# SCore-SR1_2024-11-10.net
KiCad netlist of a schematic drawn in Altium Designer
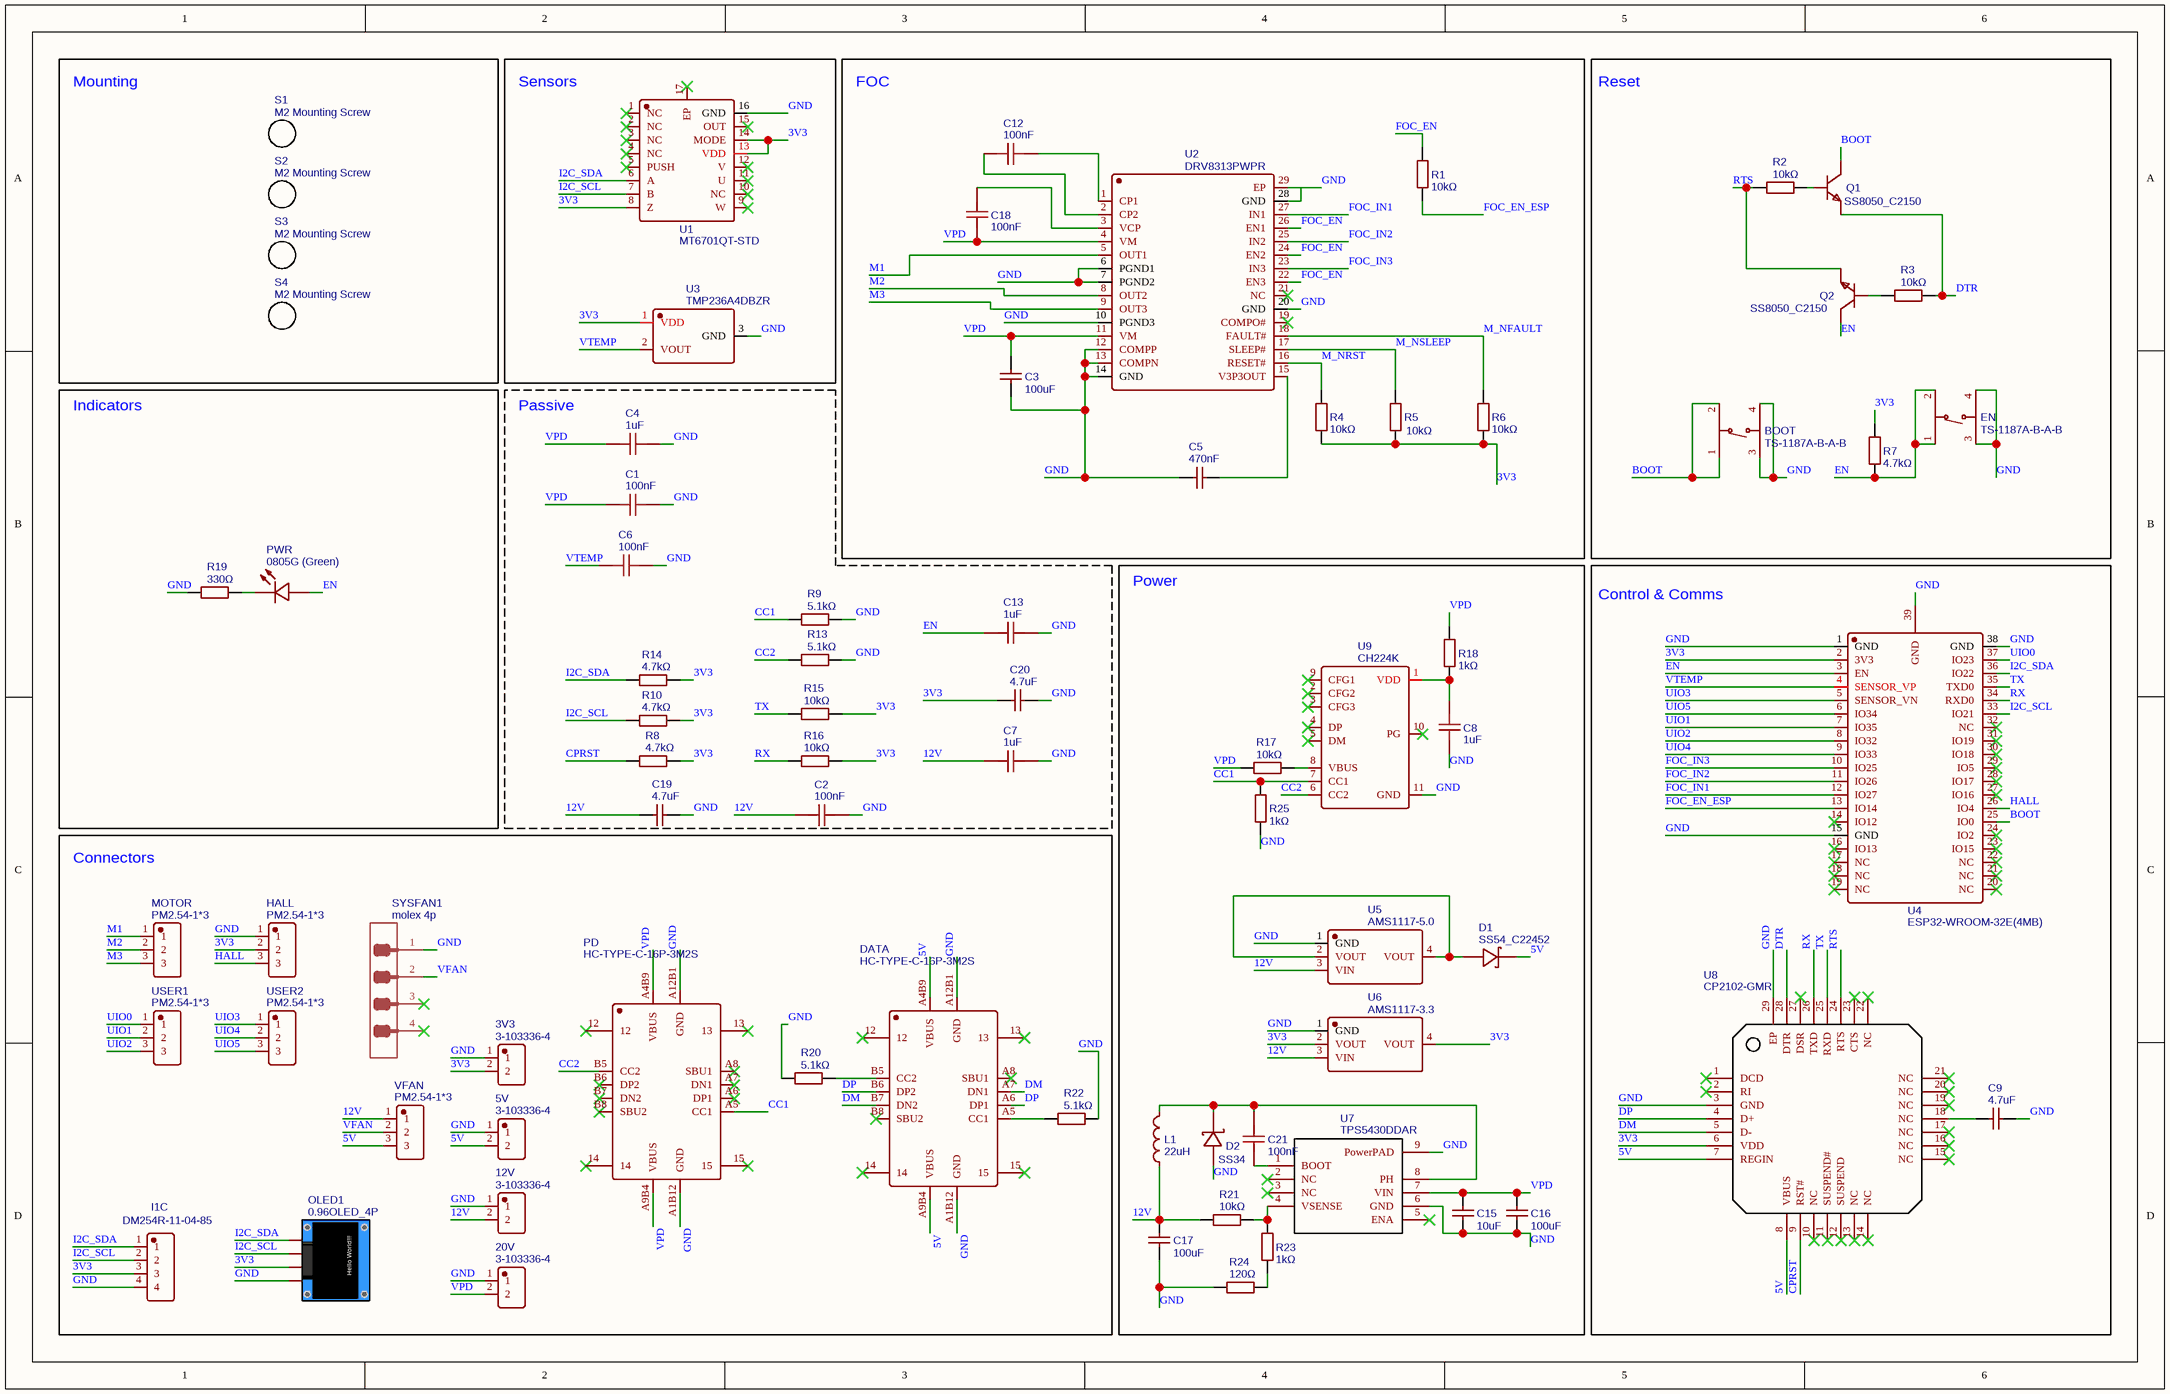
[diagram p0: SCore-SR1_2024-11-10.schdoc]

(export (version "E")
  (design (tool "Eeschema 10.0.6"))
  (components
    (comp (ref "3V3")
      (value "3-103336-4")
      (fields (field (name "MANUFACTURER") "TE Connectivity(泰科电子)") (field (name "CONTRIBUTOR") "lcsc"))
      (libsource (lib "altium-import") (part "root_0_3-103336-4_"))
    )
    (comp (ref "5V")
      (value "3-103336-4")
      (fields (field (name "MANUFACTURER") "TE Connectivity(泰科电子)") (field (name "CONTRIBUTOR") "lcsc"))
      (libsource (lib "altium-import") (part "root_0_3-103336-4_"))
    )
    (comp (ref "12V")
      (value "3-103336-4")
      (fields (field (name "MANUFACTURER") "TE Connectivity(泰科电子)") (field (name "CONTRIBUTOR") "lcsc"))
      (libsource (lib "altium-import") (part "root_0_3-103336-4_"))
    )
    (comp (ref "20V")
      (value "3-103336-4")
      (fields (field (name "MANUFACTURER") "TE Connectivity(泰科电子)") (field (name "CONTRIBUTOR") "lcsc"))
      (libsource (lib "altium-import") (part "root_0_3-103336-4_"))
    )
    (comp (ref "BOOT")
      (value "TS-1187A-B-A-B")
      (fields (field (name "MANUFACTURER") "XKB Connectivity(中国星坤)") (field (name "CONTRIBUTOR") "LCSC"))
      (libsource (lib "altium-import") (part "root_1_TS-1187A-B-A-B_"))
    )
    (comp (ref "C1")
      (value "100nF")
      (fields
        (field (name "MANUFACTURER") "YAGEO(国巨)")
        (field (name "MANUFACTURER PART") "CC0603KRX7R9BB104")
      )
      (libsource (lib "altium-import") (part "root_0_100nF_"))
    )
    (comp (ref "C2")
      (value "100nF")
      (fields
        (field (name "MANUFACTURER") "YAGEO(国巨)")
        (field (name "MANUFACTURER PART") "CC0603KRX7R9BB104")
      )
      (libsource (lib "altium-import") (part "root_0_100nF_"))
    )
    (comp (ref "C3")
      (value "100uF")
      (fields
        (field (name "MANUFACTURER PART") "CL31A107MQHNNNE")
        (field (name "MANUFACTURER") "SAMSUNG(三星)")
      )
      (libsource (lib "altium-import") (part "root_1_100uF_"))
    )
    (comp (ref "C4")
      (value "1uF")
      (fields
        (field (name "MANUFACTURER PART") "CL10A105KB8NNNC")
        (field (name "MANUFACTURER") "SAMSUNG(三星)")
      )
      (libsource (lib "altium-import") (part "root_0_1uF_"))
    )
    (comp (ref "C5")
      (value "470nF")
      (fields
        (field (name "MANUFACTURER PART") "CL21B474KBFNNNE")
        (field (name "MANUFACTURER") "SAMSUNG(三星)")
        (field (name "CONTRIBUTOR") "eisendev")
      )
      (libsource (lib "altium-import") (part "root_3_470nF_"))
    )
    (comp (ref "C6")
      (value "100nF")
      (fields
        (field (name "MANUFACTURER") "YAGEO(国巨)")
        (field (name "MANUFACTURER PART") "CC0603KRX7R9BB104")
      )
      (libsource (lib "altium-import") (part "root_0_100nF_"))
    )
    (comp (ref "C7")
      (value "1uF")
      (fields
        (field (name "MANUFACTURER PART") "CL10A105KB8NNNC")
        (field (name "MANUFACTURER") "SAMSUNG(三星)")
      )
      (libsource (lib "altium-import") (part "root_0_1uF_"))
    )
    (comp (ref "C8")
      (value "1uF")
      (fields
        (field (name "MANUFACTURER PART") "CL10A105KB8NNNC")
        (field (name "MANUFACTURER") "SAMSUNG(三星)")
      )
      (libsource (lib "altium-import") (part "root_1_1uF_"))
    )
    (comp (ref "C9")
      (value "4.7uF")
      (fields
        (field (name "MANUFACTURER PART") "CL21A475KAQNNNE")
        (field (name "MANUFACTURER") "SAMSUNG(三星)")
      )
      (libsource (lib "altium-import") (part "root_0_4.7uF_"))
    )
    (comp (ref "C12")
      (value "100nF")
      (fields
        (field (name "MANUFACTURER") "YAGEO(国巨)")
        (field (name "MANUFACTURER PART") "CC0603KRX7R9BB104")
      )
      (libsource (lib "altium-import") (part "root_0_100nF_"))
    )
    (comp (ref "C13")
      (value "1uF")
      (fields
        (field (name "MANUFACTURER PART") "CL10A105KB8NNNC")
        (field (name "MANUFACTURER") "SAMSUNG(三星)")
      )
      (libsource (lib "altium-import") (part "root_0_1uF_"))
    )
    (comp (ref "C15")
      (value "10uF")
      (fields
        (field (name "MANUFACTURER PART") "CL31A106KBHNNNE")
        (field (name "MANUFACTURER") "SAMSUNG(三星)")
      )
      (libsource (lib "altium-import") (part "root_1_10uF_"))
    )
    (comp (ref "C16")
      (value "100uF")
      (fields
        (field (name "MANUFACTURER PART") "CL31A107MQHNNNE")
        (field (name "MANUFACTURER") "SAMSUNG(三星)")
      )
      (libsource (lib "altium-import") (part "root_1_100uF_"))
    )
    (comp (ref "C17")
      (value "100uF")
      (fields
        (field (name "MANUFACTURER PART") "CL31A107MQHNNNE")
        (field (name "MANUFACTURER") "SAMSUNG(三星)")
      )
      (libsource (lib "altium-import") (part "root_1_100uF_"))
    )
    (comp (ref "C18")
      (value "100nF")
      (fields
        (field (name "MANUFACTURER") "YAGEO(国巨)")
        (field (name "MANUFACTURER PART") "CC0603KRX7R9BB104")
      )
      (libsource (lib "altium-import") (part "root_1_100nF_"))
    )
    (comp (ref "C19")
      (value "4.7uF")
      (fields
        (field (name "MANUFACTURER PART") "CL21A475KAQNNNE")
        (field (name "MANUFACTURER") "SAMSUNG(三星)")
      )
      (libsource (lib "altium-import") (part "root_0_4.7uF_"))
    )
    (comp (ref "C20")
      (value "4.7uF")
      (fields
        (field (name "MANUFACTURER PART") "CL21A475KAQNNNE")
        (field (name "MANUFACTURER") "SAMSUNG(三星)")
      )
      (libsource (lib "altium-import") (part "root_0_4.7uF_"))
    )
    (comp (ref "C21")
      (value "100nF")
      (fields
        (field (name "MANUFACTURER") "YAGEO(国巨)")
        (field (name "MANUFACTURER PART") "CC0603KRX7R9BB104")
      )
      (libsource (lib "altium-import") (part "root_3_100nF_"))
    )
    (comp (ref "D1")
      (value "SS54_C22452")
      (fields
        (field (name "MANUFACTURER PART") "SS54")
        (field (name "MANUFACTURER") "MDD")
        (field (name "CONTRIBUTOR") "mtz8302")
      )
      (libsource (lib "altium-import") (part "root_0_SS54_C22452_"))
    )
    (comp (ref "D2")
      (value "SS34")
      (fields (field (name "MANUFACTURER") "MDD(辰达半导体)"))
      (libsource (lib "altium-import") (part "root_3_SS34_"))
    )
    (comp (ref "DATA")
      (value "HC-TYPE-C-16P-3M2S")
      (fields (field (name "MANUFACTURER") "HC(虹成电子)") (field (name "CONTRIBUTOR") "lcsc"))
      (libsource (lib "altium-import") (part "root_0_HC-TYPE-C-16P-3M2S_"))
    )
    (comp (ref "EN")
      (value "TS-1187A-B-A-B")
      (fields (field (name "MANUFACTURER") "XKB Connectivity(中国星坤)") (field (name "CONTRIBUTOR") "LCSC"))
      (libsource (lib "altium-import") (part "root_1_TS-1187A-B-A-B_"))
    )
    (comp (ref "HALL")
      (value "PM2.54-1*3")
      (fields (field (name "MANUFACTURER") "ZHOURI(洲日)") (field (name "CONTRIBUTOR") "lcsc"))
      (libsource (lib "altium-import") (part "root_0_PM2.54-1*3_"))
    )
    (comp (ref "I1C")
      (value "DM254R-11-04-85")
      (fields (field (name "MANUFACTURER") "DEALON(德艺隆)") (field (name "CONTRIBUTOR") "LCSC"))
      (libsource (lib "altium-import") (part "root_0_DM254R-11-04-85_"))
    )
    (comp (ref "L1")
      (value "22uH")
      (fields (field (name "MANUFACTURER") "FH(风华)") (field (name "MANUFACTURER PART") "PRS4018-220MT"))
      (libsource (lib "altium-import") (part "root_1_22uH_"))
    )
    (comp (ref "MOTOR")
      (value "PM2.54-1*3")
      (fields (field (name "MANUFACTURER") "ZHOURI(洲日)") (field (name "CONTRIBUTOR") "lcsc"))
      (libsource (lib "altium-import") (part "root_0_PM2.54-1*3_"))
    )
    (comp (ref "OLED1")
      (value "0.96OLED_4P")
      (fields (field (name "CONTRIBUTOR") "LCEDA_Lib"))
      (libsource (lib "altium-import") (part "root_3_0.96OLED_4P_"))
    )
    (comp (ref "PD")
      (value "HC-TYPE-C-16P-3M2S")
      (fields (field (name "MANUFACTURER") "HC(虹成电子)") (field (name "CONTRIBUTOR") "lcsc"))
      (libsource (lib "altium-import") (part "root_0_HC-TYPE-C-16P-3M2S_"))
    )
    (comp (ref "PWR")
      (value "0805G (Green)")
      (fields (field (name "MANUFACTURER") "KENTO") (field (name "MANUFACTURER PART") "KT-0805G"))
      (libsource (lib "altium-import") (part "root_0_0805G (Green)_"))
    )
    (comp (ref "Q1")
      (value "SS8050_C2150")
      (fields (field (name "MANUFACTURER") "CJ(江苏长电/长晶)") (field (name "MANUFACTURER PART") "SS8050"))
      (libsource (lib "altium-import") (part "root_0_SS8050_C2150_"))
    )
    (comp (ref "Q2")
      (value "SS8050_C2150")
      (fields (field (name "MANUFACTURER") "CJ(江苏长电/长晶)") (field (name "MANUFACTURER PART") "SS8050"))
      (libsource (lib "altium-import") (part "root_2_SS8050_C2150_"))
    )
    (comp (ref "R1")
      (value "10kΩ")
      (fields (field (name "MANUFACTURER") "UniOhm") (field (name "MANUFACTURER PART") "0603WAF4701T5E"))
      (libsource (lib "altium-import") (part "root_1_10kΩ_"))
    )
    (comp (ref "R2")
      (value "10kΩ")
      (fields
        (field (name "MANUFACTURER") "UNI-ROYAL(厚声)")
        (field (name "MANUFACTURER PART") "1206W4F1002T5E")
      )
      (libsource (lib "altium-import") (part "root_0_10kΩ_"))
    )
    (comp (ref "R3")
      (value "10kΩ")
      (fields
        (field (name "MANUFACTURER") "UNI-ROYAL(厚声)")
        (field (name "MANUFACTURER PART") "1206W4F1002T5E")
      )
      (libsource (lib "altium-import") (part "root_0_10kΩ_"))
    )
    (comp (ref "R4")
      (value "10kΩ")
      (fields (field (name "MANUFACTURER") "UniOhm") (field (name "MANUFACTURER PART") "0603WAF4701T5E"))
      (libsource (lib "altium-import") (part "root_1_10kΩ_"))
    )
    (comp (ref "R5")
      (value "10kΩ")
      (fields (field (name "MANUFACTURER") "UniOhm") (field (name "MANUFACTURER PART") "0603WAF4701T5E"))
      (libsource (lib "altium-import") (part "root_1_10kΩ_"))
    )
    (comp (ref "R6")
      (value "10kΩ")
      (fields (field (name "MANUFACTURER") "UniOhm") (field (name "MANUFACTURER PART") "0603WAF4701T5E"))
      (libsource (lib "altium-import") (part "root_1_10kΩ_"))
    )
    (comp (ref "R7")
      (value "4.7kΩ")
      (fields
        (field (name "MANUFACTURER") "UNI-ROYAL(厚声)")
        (field (name "MANUFACTURER PART") "0805W8F4701T5E")
      )
      (libsource (lib "altium-import") (part "root_1_4.7kΩ_"))
    )
    (comp (ref "R8")
      (value "4.7kΩ")
      (fields
        (field (name "MANUFACTURER") "UNI-ROYAL(厚声)")
        (field (name "MANUFACTURER PART") "0805W8F4701T5E")
      )
      (libsource (lib "altium-import") (part "root_2_4.7kΩ_"))
    )
    (comp (ref "R9")
      (value "5.1kΩ")
      (fields
        (field (name "MANUFACTURER PART") "0603WAF5101T5E")
        (field (name "MANUFACTURER") "UNI-ROYAL(厚声)")
      )
      (libsource (lib "altium-import") (part "root_0_5.1kΩ_"))
    )
    (comp (ref "R10")
      (value "4.7kΩ")
      (fields
        (field (name "MANUFACTURER") "UNI-ROYAL(厚声)")
        (field (name "MANUFACTURER PART") "0805W8F4701T5E")
      )
      (libsource (lib "altium-import") (part "root_2_4.7kΩ_"))
    )
    (comp (ref "R13")
      (value "5.1kΩ")
      (fields
        (field (name "MANUFACTURER PART") "0603WAF5101T5E")
        (field (name "MANUFACTURER") "UNI-ROYAL(厚声)")
      )
      (libsource (lib "altium-import") (part "root_0_5.1kΩ_"))
    )
    (comp (ref "R14")
      (value "4.7kΩ")
      (fields
        (field (name "MANUFACTURER") "UNI-ROYAL(厚声)")
        (field (name "MANUFACTURER PART") "0805W8F4701T5E")
      )
      (libsource (lib "altium-import") (part "root_2_4.7kΩ_"))
    )
    (comp (ref "R15")
      (value "10kΩ")
      (fields (field (name "MANUFACTURER") "UniOhm") (field (name "MANUFACTURER PART") "0603WAF4701T5E"))
      (libsource (lib "altium-import") (part "root_2_10kΩ_"))
    )
    (comp (ref "R16")
      (value "10kΩ")
      (fields (field (name "MANUFACTURER") "UniOhm") (field (name "MANUFACTURER PART") "0603WAF4701T5E"))
      (libsource (lib "altium-import") (part "root_2_10kΩ_"))
    )
    (comp (ref "R17")
      (value "10kΩ")
      (fields (field (name "MANUFACTURER") "UniOhm") (field (name "MANUFACTURER PART") "0603WAF4701T5E"))
      (libsource (lib "altium-import") (part "root_2_10kΩ_"))
    )
    (comp (ref "R18")
      (value "1kΩ")
      (fields
        (field (name "MANUFACTURER") "UNI-ROYAL(厚声)")
        (field (name "MANUFACTURER PART") "0402WGF1001TCE")
      )
      (libsource (lib "altium-import") (part "root_1_1kΩ_"))
    )
    (comp (ref "R19")
      (value "330Ω")
      (fields
        (field (name "MANUFACTURER") "UNI-ROYAL(厚声)")
        (field (name "MANUFACTURER PART") "0805W8F3300T5E")
      )
      (libsource (lib "altium-import") (part "root_0_330Ω_"))
    )
    (comp (ref "R20")
      (value "5.1kΩ")
      (fields
        (field (name "MANUFACTURER PART") "0603WAF5101T5E")
        (field (name "MANUFACTURER") "UNI-ROYAL(厚声)")
      )
      (libsource (lib "altium-import") (part "root_0_5.1kΩ_"))
    )
    (comp (ref "R21")
      (value "10kΩ")
      (fields
        (field (name "MANUFACTURER") "UNI-ROYAL(厚声)")
        (field (name "MANUFACTURER PART") "0805W8F1002T5E")
      )
      (libsource (lib "altium-import") (part "root_2_10kΩ_"))
    )
    (comp (ref "R22")
      (value "5.1kΩ")
      (fields
        (field (name "MANUFACTURER PART") "0603WAF5101T5E")
        (field (name "MANUFACTURER") "UNI-ROYAL(厚声)")
      )
      (libsource (lib "altium-import") (part "root_0_5.1kΩ_"))
    )
    (comp (ref "R23")
      (value "1kΩ")
      (fields
        (field (name "MANUFACTURER") "UNI-ROYAL(厚声)")
        (field (name "MANUFACTURER PART") "0402WGF1001TCE")
      )
      (libsource (lib "altium-import") (part "root_1_1kΩ_"))
    )
    (comp (ref "R24")
      (value "120Ω")
      (fields
        (field (name "MANUFACTURER") "UNI-ROYAL(厚声)")
        (field (name "MANUFACTURER PART") "0805W8F1200T5E")
      )
      (libsource (lib "altium-import") (part "root_0_120Ω_"))
    )
    (comp (ref "R25")
      (value "1kΩ")
      (fields
        (field (name "MANUFACTURER") "UNI-ROYAL(厚声)")
        (field (name "MANUFACTURER PART") "0402WGF1001TCE")
      )
      (libsource (lib "altium-import") (part "root_1_1kΩ_"))
    )
    (comp (ref "S1")
      (value "M2 Mounting Screw")
      (fields (field (name "CONTRIBUTOR") "Dayat -"))
      (libsource (lib "altium-import") (part "root_0_M2 Mounting Screw_"))
    )
    (comp (ref "S2")
      (value "M2 Mounting Screw")
      (fields (field (name "CONTRIBUTOR") "Dayat -"))
      (libsource (lib "altium-import") (part "root_0_M2 Mounting Screw_"))
    )
    (comp (ref "S3")
      (value "M2 Mounting Screw")
      (fields (field (name "CONTRIBUTOR") "Dayat -"))
      (libsource (lib "altium-import") (part "root_0_M2 Mounting Screw_"))
    )
    (comp (ref "S4")
      (value "M2 Mounting Screw")
      (fields (field (name "CONTRIBUTOR") "Dayat -"))
      (libsource (lib "altium-import") (part "root_0_M2 Mounting Screw_"))
    )
    (comp (ref "SYSFAN1")
      (value "molex 4p")
      (fields (field (name "CONTRIBUTOR") "delil1220"))
      (libsource (lib "altium-import") (part "root_0_molex 4p_"))
    )
    (comp (ref "U1")
      (value "MT6701QT-STD")
      (fields (field (name "MANUFACTURER") "MagnTek(麦歌恩)") (field (name "CONTRIBUTOR") "LCSC"))
      (libsource (lib "altium-import") (part "root_0_MT6701QT-STD_"))
    )
    (comp (ref "U2")
      (value "DRV8313PWPR")
      (fields (field (name "MANUFACTURER") "Texas Instruments") (field (name "CONTRIBUTOR") "LCSC"))
      (libsource (lib "altium-import") (part "root_0_DRV8313PWPR_"))
    )
    (comp (ref "U3")
      (value "TMP236A4DBZR")
      (fields (field (name "MANUFACTURER") "TI(德州仪器)") (field (name "CONTRIBUTOR") "LCSC"))
      (libsource (lib "altium-import") (part "root_0_TMP236A4DBZR_"))
    )
    (comp (ref "U4")
      (value "ESP32-WROOM-32E(4MB)")
      (fields
        (field (name "MANUFACTURER") "ESPRESSIF(乐鑫)")
        (field (name "MANUFACTURER PART") "ESP32-WROOM-32E-N4")
        (field (name "CONTRIBUTOR") "LCSC")
      )
      (libsource (lib "altium-import") (part "root_0_ESP32-WROOM-32E(4MB)_"))
    )
    (comp (ref "U5")
      (value "AMS1117-5.0")
      (fields (field (name "MANUFACTURER") "AMS"))
      (libsource (lib "altium-import") (part "root_0_AMS1117-5.0_"))
    )
    (comp (ref "U6")
      (value "AMS1117-3.3")
      (fields (field (name "MANUFACTURER") "AMS"))
      (libsource (lib "altium-import") (part "root_0_AMS1117-3.3_"))
    )
    (comp (ref "U7")
      (value "TPS5430DDAR")
      (fields (field (name "MANUFACTURER") "TI(德州仪器)"))
      (libsource (lib "altium-import") (part "root_0_TPS5430DDAR_"))
    )
    (comp (ref "U8")
      (value "CP2102-GMR")
      (fields (field (name "MANUFACTURER") "SKYWORKS/SILICON LABS(芯科)"))
      (libsource (lib "altium-import") (part "root_0_CP2102-GMR_"))
    )
    (comp (ref "U9")
      (value "CH224K")
      (fields (field (name "MANUFACTURER") "WCH(南京沁恒)") (field (name "CONTRIBUTOR") "lcsc"))
      (libsource (lib "altium-import") (part "root_0_CH224K_"))
    )
    (comp (ref "USER1")
      (value "PM2.54-1*3")
      (fields (field (name "MANUFACTURER") "ZHOURI(洲日)") (field (name "CONTRIBUTOR") "lcsc"))
      (libsource (lib "altium-import") (part "root_0_PM2.54-1*3_"))
    )
    (comp (ref "USER2")
      (value "PM2.54-1*3")
      (fields (field (name "MANUFACTURER") "ZHOURI(洲日)") (field (name "CONTRIBUTOR") "lcsc"))
      (libsource (lib "altium-import") (part "root_0_PM2.54-1*3_"))
    )
    (comp (ref "VFAN")
      (value "PM2.54-1*3")
      (fields (field (name "MANUFACTURER") "ZHOURI(洲日)") (field (name "CONTRIBUTOR") "lcsc"))
      (libsource (lib "altium-import") (part "root_0_PM2.54-1*3_"))
    )
  )
  (nets
    (net (code "1") (name "/3V3") (class "Default")
      (node (ref "3V3") (pin "2") (pinfunction "2_2") (pintype "passive"))
      (node (ref "C20") (pin "1") (pinfunction "1_1") (pintype "passive"))
      (node (ref "HALL") (pin "2") (pinfunction "2_2") (pintype "passive"))
      (node (ref "I1C") (pin "3") (pinfunction "3_3") (pintype "passive"))
      (node (ref "OLED1") (pin "3") (pinfunction "3_3") (pintype "passive"))
      (node (ref "R10") (pin "1") (pinfunction "1_1") (pintype "passive"))
      (node (ref "R14") (pin "1") (pinfunction "1_1") (pintype "passive"))
      (node (ref "R15") (pin "1") (pinfunction "1_1") (pintype "passive"))
      (node (ref "R16") (pin "1") (pinfunction "1_1") (pintype "passive"))
      (node (ref "R4") (pin "1") (pinfunction "1_1") (pintype "passive"))
      (node (ref "R5") (pin "1") (pinfunction "1_1") (pintype "passive"))
      (node (ref "R6") (pin "1") (pinfunction "1_1") (pintype "passive"))
      (node (ref "R7") (pin "2") (pinfunction "2_2") (pintype "passive"))
      (node (ref "R8") (pin "1") (pinfunction "1_1") (pintype "passive"))
      (node (ref "U1") (pin "13") (pinfunction "VDD_13") (pintype "passive"))
      (node (ref "U1") (pin "14") (pinfunction "MODE_14") (pintype "passive"))
      (node (ref "U1") (pin "8") (pinfunction "Z_8") (pintype "passive"))
      (node (ref "U3") (pin "1") (pinfunction "VDD_1") (pintype "passive"))
      (node (ref "U4") (pin "2") (pinfunction "3V3_2") (pintype "passive"))
      (node (ref "U6") (pin "2") (pinfunction "VOUT_2") (pintype "passive"))
      (node (ref "U6") (pin "4") (pinfunction "VOUT_4") (pintype "passive"))
      (node (ref "U8") (pin "6") (pinfunction "VDD_6") (pintype "passive"))
    )
    (net (code "2") (name "/5V") (class "Default")
      (node (ref "5V") (pin "2") (pinfunction "2_2") (pintype "passive"))
      (node (ref "D1") (pin "2") (pinfunction "K_2") (pintype "passive"))
      (node (ref "DATA") (pin "A4B9") (pinfunction "VBUS_A4B9") (pintype "passive"))
      (node (ref "DATA") (pin "A9B4") (pinfunction "VBUS_A9B4") (pintype "passive"))
      (node (ref "U8") (pin "7") (pinfunction "REGIN_7") (pintype "passive"))
      (node (ref "U8") (pin "8") (pinfunction "VBUS_8") (pintype "passive"))
      (node (ref "VFAN") (pin "3") (pinfunction "3_3") (pintype "passive"))
    )
    (net (code "3") (name "/12V") (class "Default")
      (node (ref "12V") (pin "2") (pinfunction "2_2") (pintype "passive"))
      (node (ref "C17") (pin "2") (pinfunction "2_2") (pintype "passive"))
      (node (ref "C19") (pin "1") (pinfunction "1_1") (pintype "passive"))
      (node (ref "C2") (pin "1") (pinfunction "1_1") (pintype "passive"))
      (node (ref "C7") (pin "1") (pinfunction "1_1") (pintype "passive"))
      (node (ref "L1") (pin "1") (pinfunction "1_1") (pintype "passive"))
      (node (ref "R21") (pin "2") (pinfunction "2_2") (pintype "passive"))
      (node (ref "U5") (pin "3") (pinfunction "VIN_3") (pintype "passive"))
      (node (ref "U6") (pin "3") (pinfunction "VIN_3") (pintype "passive"))
      (node (ref "VFAN") (pin "1") (pinfunction "1_1") (pintype "passive"))
    )
    (net (code "4") (name "/BOOT") (class "Default")
      (node (ref "BOOT") (pin "1") (pinfunction "A_1") (pintype "passive"))
      (node (ref "BOOT") (pin "2") (pinfunction "B_2") (pintype "passive"))
      (node (ref "Q1") (pin "3") (pinfunction "C_3") (pintype "passive"))
      (node (ref "U4") (pin "25") (pinfunction "IO0_25") (pintype "passive"))
    )
    (net (code "5") (name "/CC1") (class "Default")
      (node (ref "PD") (pin "A5") (pinfunction "CC1_A5") (pintype "passive"))
      (node (ref "R25") (pin "2") (pinfunction "2_2") (pintype "passive"))
      (node (ref "R9") (pin "1") (pinfunction "1_1") (pintype "passive"))
      (node (ref "U9") (pin "7") (pinfunction "CC1_7") (pintype "passive"))
    )
    (net (code "6") (name "/CC2") (class "Default")
      (node (ref "PD") (pin "B5") (pinfunction "CC2_B5") (pintype "passive"))
      (node (ref "R13") (pin "1") (pinfunction "1_1") (pintype "passive"))
      (node (ref "U9") (pin "6") (pinfunction "CC2_6") (pintype "passive"))
    )
    (net (code "7") (name "/CPRST") (class "Default")
      (node (ref "R8") (pin "2") (pinfunction "2_2") (pintype "passive"))
      (node (ref "U8") (pin "9") (pinfunction "RST#_9") (pintype "passive"))
    )
    (net (code "8") (name "/DM") (class "Default")
      (node (ref "DATA") (pin "A7") (pinfunction "DN1_A7") (pintype "passive"))
      (node (ref "DATA") (pin "B7") (pinfunction "DN2_B7") (pintype "passive"))
      (node (ref "U8") (pin "5") (pinfunction "D-_5") (pintype "passive"))
    )
    (net (code "9") (name "/DP") (class "Default")
      (node (ref "DATA") (pin "A6") (pinfunction "DP1_A6") (pintype "passive"))
      (node (ref "DATA") (pin "B6") (pinfunction "DP2_B6") (pintype "passive"))
      (node (ref "U8") (pin "4") (pinfunction "D+_4") (pintype "passive"))
    )
    (net (code "10") (name "/DTR") (class "Default")
      (node (ref "Q1") (pin "2") (pinfunction "E_2") (pintype "passive"))
      (node (ref "R3") (pin "2") (pinfunction "2_2") (pintype "passive"))
      (node (ref "U8") (pin "28") (pinfunction "DTR_28") (pintype "passive"))
    )
    (net (code "11") (name "/EN") (class "Default")
      (node (ref "C13") (pin "1") (pinfunction "1_1") (pintype "passive"))
      (node (ref "EN") (pin "1") (pinfunction "A_1") (pintype "passive"))
      (node (ref "EN") (pin "2") (pinfunction "B_2") (pintype "passive"))
      (node (ref "PWR") (pin "1") (pinfunction "A_1") (pintype "passive"))
      (node (ref "Q2") (pin "3") (pinfunction "C_3") (pintype "passive"))
      (node (ref "R7") (pin "1") (pinfunction "1_1") (pintype "passive"))
      (node (ref "U4") (pin "3") (pinfunction "EN_3") (pintype "passive"))
    )
    (net (code "12") (name "/FOC_EN") (class "Default")
      (node (ref "R1") (pin "2") (pinfunction "2_2") (pintype "passive"))
      (node (ref "U2") (pin "22") (pinfunction "EN3_22") (pintype "passive"))
      (node (ref "U2") (pin "24") (pinfunction "EN2_24") (pintype "passive"))
      (node (ref "U2") (pin "26") (pinfunction "EN1_26") (pintype "passive"))
    )
    (net (code "13") (name "/FOC_EN_ESP") (class "Default")
      (node (ref "R1") (pin "1") (pinfunction "1_1") (pintype "passive"))
      (node (ref "U4") (pin "13") (pinfunction "IO14_13") (pintype "passive"))
    )
    (net (code "14") (name "/FOC_IN1") (class "Default")
      (node (ref "U2") (pin "27") (pinfunction "IN1_27") (pintype "passive"))
      (node (ref "U4") (pin "12") (pinfunction "IO27_12") (pintype "passive"))
    )
    (net (code "15") (name "/FOC_IN2") (class "Default")
      (node (ref "U2") (pin "25") (pinfunction "IN2_25") (pintype "passive"))
      (node (ref "U4") (pin "11") (pinfunction "IO26_11") (pintype "passive"))
    )
    (net (code "16") (name "/FOC_IN3") (class "Default")
      (node (ref "U2") (pin "23") (pinfunction "IN3_23") (pintype "passive"))
      (node (ref "U4") (pin "10") (pinfunction "IO25_10") (pintype "passive"))
    )
    (net (code "17") (name "/GND") (class "Default")
      (node (ref "12V") (pin "1") (pinfunction "1_1") (pintype "passive"))
      (node (ref "20V") (pin "1") (pinfunction "1_1") (pintype "passive"))
      (node (ref "3V3") (pin "1") (pinfunction "1_1") (pintype "passive"))
      (node (ref "5V") (pin "1") (pinfunction "1_1") (pintype "passive"))
      (node (ref "BOOT") (pin "3") (pinfunction "C_3") (pintype "passive"))
      (node (ref "BOOT") (pin "4") (pinfunction "D_4") (pintype "passive"))
      (node (ref "C1") (pin "2") (pinfunction "2_2") (pintype "passive"))
      (node (ref "C13") (pin "2") (pinfunction "2_2") (pintype "passive"))
      (node (ref "C15") (pin "1") (pinfunction "1_1") (pintype "passive"))
      (node (ref "C16") (pin "1") (pinfunction "1_1") (pintype "passive"))
      (node (ref "C17") (pin "1") (pinfunction "1_1") (pintype "passive"))
      (node (ref "C19") (pin "2") (pinfunction "2_2") (pintype "passive"))
      (node (ref "C2") (pin "2") (pinfunction "2_2") (pintype "passive"))
      (node (ref "C20") (pin "2") (pinfunction "2_2") (pintype "passive"))
      (node (ref "C3") (pin "1") (pinfunction "1_1") (pintype "passive"))
      (node (ref "C4") (pin "2") (pinfunction "2_2") (pintype "passive"))
      (node (ref "C5") (pin "1") (pinfunction "1_1") (pintype "passive"))
      (node (ref "C6") (pin "2") (pinfunction "2_2") (pintype "passive"))
      (node (ref "C7") (pin "2") (pinfunction "2_2") (pintype "passive"))
      (node (ref "C8") (pin "1") (pinfunction "1_1") (pintype "passive"))
      (node (ref "C9") (pin "2") (pinfunction "2_2") (pintype "passive"))
      (node (ref "D2") (pin "2") (pinfunction "A_2") (pintype "passive"))
      (node (ref "DATA") (pin "A12B1") (pinfunction "GND_A12B1") (pintype "passive"))
      (node (ref "DATA") (pin "A1B12") (pinfunction "GND_A1B12") (pintype "passive"))
      (node (ref "EN") (pin "3") (pinfunction "C_3") (pintype "passive"))
      (node (ref "EN") (pin "4") (pinfunction "D_4") (pintype "passive"))
      (node (ref "HALL") (pin "1") (pinfunction "1_1") (pintype "passive"))
      (node (ref "I1C") (pin "4") (pinfunction "4_4") (pintype "passive"))
      (node (ref "OLED1") (pin "4") (pinfunction "4_4") (pintype "passive"))
      (node (ref "PD") (pin "A12B1") (pinfunction "GND_A12B1") (pintype "passive"))
      (node (ref "PD") (pin "A1B12") (pinfunction "GND_A1B12") (pintype "passive"))
      (node (ref "R13") (pin "2") (pinfunction "2_2") (pintype "passive"))
      (node (ref "R19") (pin "1") (pinfunction "1_1") (pintype "passive"))
      (node (ref "R20") (pin "1") (pinfunction "1_1") (pintype "passive"))
      (node (ref "R22") (pin "2") (pinfunction "2_2") (pintype "passive"))
      (node (ref "R24") (pin "1") (pinfunction "1_1") (pintype "passive"))
      (node (ref "R25") (pin "1") (pinfunction "1_1") (pintype "passive"))
      (node (ref "R9") (pin "2") (pinfunction "2_2") (pintype "passive"))
      (node (ref "SYSFAN1") (pin "1") (pinfunction "1_1") (pintype "passive"))
      (node (ref "U1") (pin "16") (pinfunction "GND_16") (pintype "passive"))
      (node (ref "U2") (pin "10") (pinfunction "PGND3_10") (pintype "passive"))
      (node (ref "U2") (pin "12") (pinfunction "COMPP_12") (pintype "passive"))
      (node (ref "U2") (pin "13") (pinfunction "COMPN_13") (pintype "passive"))
      (node (ref "U2") (pin "14") (pinfunction "GND_14") (pintype "passive"))
      (node (ref "U2") (pin "20") (pinfunction "GND_20") (pintype "passive"))
      (node (ref "U2") (pin "28") (pinfunction "GND_28") (pintype "passive"))
      (node (ref "U2") (pin "29") (pinfunction "EP_29") (pintype "passive"))
      (node (ref "U2") (pin "6") (pinfunction "PGND1_6") (pintype "passive"))
      (node (ref "U2") (pin "7") (pinfunction "PGND2_7") (pintype "passive"))
      (node (ref "U3") (pin "3") (pinfunction "GND_3") (pintype "passive"))
      (node (ref "U4") (pin "1") (pinfunction "GND_1") (pintype "passive"))
      (node (ref "U4") (pin "15") (pinfunction "GND_15") (pintype "passive"))
      (node (ref "U4") (pin "38") (pinfunction "GND_38") (pintype "passive"))
      (node (ref "U4") (pin "39") (pinfunction "GND_39") (pintype "passive"))
      (node (ref "U5") (pin "1") (pinfunction "GND_1") (pintype "passive"))
      (node (ref "U6") (pin "1") (pinfunction "GND_1") (pintype "passive"))
      (node (ref "U7") (pin "6") (pinfunction "GND_6") (pintype "passive"))
      (node (ref "U7") (pin "9") (pinfunction "PowerPAD_9") (pintype "passive"))
      (node (ref "U8") (pin "29") (pinfunction "EP_29") (pintype "passive"))
      (node (ref "U8") (pin "3") (pinfunction "GND_3") (pintype "passive"))
      (node (ref "U9") (pin "11") (pinfunction "GND_11") (pintype "passive"))
    )
    (net (code "18") (name "/HALL") (class "Default")
      (node (ref "HALL") (pin "3") (pinfunction "3_3") (pintype "passive"))
      (node (ref "U4") (pin "26") (pinfunction "IO4_26") (pintype "passive"))
    )
    (net (code "19") (name "/I2C_SCL") (class "Default")
      (node (ref "I1C") (pin "2") (pinfunction "2_2") (pintype "passive"))
      (node (ref "OLED1") (pin "2") (pinfunction "2_2") (pintype "passive"))
      (node (ref "R10") (pin "2") (pinfunction "2_2") (pintype "passive"))
      (node (ref "U1") (pin "7") (pinfunction "B_7") (pintype "passive"))
      (node (ref "U4") (pin "33") (pinfunction "IO21_33") (pintype "passive"))
    )
    (net (code "20") (name "/I2C_SDA") (class "Default")
      (node (ref "I1C") (pin "1") (pinfunction "1_1") (pintype "passive"))
      (node (ref "OLED1") (pin "1") (pinfunction "1_1") (pintype "passive"))
      (node (ref "R14") (pin "2") (pinfunction "2_2") (pintype "passive"))
      (node (ref "U1") (pin "6") (pinfunction "A_6") (pintype "passive"))
      (node (ref "U4") (pin "36") (pinfunction "IO22_36") (pintype "passive"))
    )
    (net (code "21") (name "/M1") (class "Default")
      (node (ref "MOTOR") (pin "1") (pinfunction "1_1") (pintype "passive"))
      (node (ref "U2") (pin "5") (pinfunction "OUT1_5") (pintype "passive"))
    )
    (net (code "22") (name "/M2") (class "Default")
      (node (ref "MOTOR") (pin "2") (pinfunction "2_2") (pintype "passive"))
      (node (ref "U2") (pin "8") (pinfunction "OUT2_8") (pintype "passive"))
    )
    (net (code "23") (name "/M3") (class "Default")
      (node (ref "MOTOR") (pin "3") (pinfunction "3_3") (pintype "passive"))
      (node (ref "U2") (pin "9") (pinfunction "OUT3_9") (pintype "passive"))
    )
    (net (code "24") (name "/M_NFAULT") (class "Default")
      (node (ref "R6") (pin "2") (pinfunction "2_2") (pintype "passive"))
      (node (ref "U2") (pin "18") (pinfunction "FAULT#_18") (pintype "passive"))
    )
    (net (code "25") (name "/M_NRST") (class "Default")
      (node (ref "R4") (pin "2") (pinfunction "2_2") (pintype "passive"))
      (node (ref "U2") (pin "16") (pinfunction "RESET#_16") (pintype "passive"))
    )
    (net (code "26") (name "/M_NSLEEP") (class "Default")
      (node (ref "R5") (pin "2") (pinfunction "2_2") (pintype "passive"))
      (node (ref "U2") (pin "17") (pinfunction "SLEEP#_17") (pintype "passive"))
    )
    (net (code "27") (name "/RTS") (class "Default")
      (node (ref "Q2") (pin "2") (pinfunction "E_2") (pintype "passive"))
      (node (ref "R2") (pin "1") (pinfunction "1_1") (pintype "passive"))
      (node (ref "U8") (pin "24") (pinfunction "RTS_24") (pintype "passive"))
    )
    (net (code "28") (name "/RX") (class "Default")
      (node (ref "R16") (pin "2") (pinfunction "2_2") (pintype "passive"))
      (node (ref "U4") (pin "34") (pinfunction "RXD0_34") (pintype "passive"))
      (node (ref "U8") (pin "26") (pinfunction "TXD_26") (pintype "passive"))
    )
    (net (code "29") (name "/TX") (class "Default")
      (node (ref "R15") (pin "2") (pinfunction "2_2") (pintype "passive"))
      (node (ref "U4") (pin "35") (pinfunction "TXD0_35") (pintype "passive"))
      (node (ref "U8") (pin "25") (pinfunction "RXD_25") (pintype "passive"))
    )
    (net (code "30") (name "/UIO0") (class "Default")
      (node (ref "U4") (pin "37") (pinfunction "IO23_37") (pintype "passive"))
      (node (ref "USER1") (pin "1") (pinfunction "1_1") (pintype "passive"))
    )
    (net (code "31") (name "/UIO1") (class "Default")
      (node (ref "U4") (pin "7") (pinfunction "IO35_7") (pintype "passive"))
      (node (ref "USER1") (pin "2") (pinfunction "2_2") (pintype "passive"))
    )
    (net (code "32") (name "/UIO2") (class "Default")
      (node (ref "U4") (pin "8") (pinfunction "IO32_8") (pintype "passive"))
      (node (ref "USER1") (pin "3") (pinfunction "3_3") (pintype "passive"))
    )
    (net (code "33") (name "/UIO3") (class "Default")
      (node (ref "U4") (pin "5") (pinfunction "SENSOR_VN_5") (pintype "passive"))
      (node (ref "USER2") (pin "1") (pinfunction "1_1") (pintype "passive"))
    )
    (net (code "34") (name "/UIO4") (class "Default")
      (node (ref "U4") (pin "9") (pinfunction "IO33_9") (pintype "passive"))
      (node (ref "USER2") (pin "2") (pinfunction "2_2") (pintype "passive"))
    )
    (net (code "35") (name "/UIO5") (class "Default")
      (node (ref "U4") (pin "6") (pinfunction "IO34_6") (pintype "passive"))
      (node (ref "USER2") (pin "3") (pinfunction "3_3") (pintype "passive"))
    )
    (net (code "36") (name "/VFAN") (class "Default")
      (node (ref "SYSFAN1") (pin "2") (pinfunction "2_2") (pintype "passive"))
      (node (ref "VFAN") (pin "2") (pinfunction "2_2") (pintype "passive"))
    )
    (net (code "37") (name "/VPD") (class "Default")
      (node (ref "20V") (pin "2") (pinfunction "2_2") (pintype "passive"))
      (node (ref "C1") (pin "1") (pinfunction "1_1") (pintype "passive"))
      (node (ref "C15") (pin "2") (pinfunction "2_2") (pintype "passive"))
      (node (ref "C16") (pin "2") (pinfunction "2_2") (pintype "passive"))
      (node (ref "C18") (pin "1") (pinfunction "1_1") (pintype "passive"))
      (node (ref "C3") (pin "2") (pinfunction "2_2") (pintype "passive"))
      (node (ref "C4") (pin "1") (pinfunction "1_1") (pintype "passive"))
      (node (ref "PD") (pin "A4B9") (pinfunction "VBUS_A4B9") (pintype "passive"))
      (node (ref "PD") (pin "A9B4") (pinfunction "VBUS_A9B4") (pintype "passive"))
      (node (ref "R17") (pin "2") (pinfunction "2_2") (pintype "passive"))
      (node (ref "R18") (pin "2") (pinfunction "2_2") (pintype "passive"))
      (node (ref "U2") (pin "11") (pinfunction "VM_11") (pintype "passive"))
      (node (ref "U2") (pin "4") (pinfunction "VM_4") (pintype "passive"))
      (node (ref "U7") (pin "7") (pinfunction "VIN_7") (pintype "passive"))
    )
    (net (code "38") (name "/VTEMP") (class "Default")
      (node (ref "C6") (pin "1") (pinfunction "1_1") (pintype "passive"))
      (node (ref "U3") (pin "2") (pinfunction "VOUT_2") (pintype "passive"))
      (node (ref "U4") (pin "4") (pinfunction "SENSOR_VP_4") (pintype "passive"))
    )
    (net (code "39") (name "Net-(C9-Pad1)") (class "Default")
      (node (ref "C9") (pin "1") (pinfunction "1_1") (pintype "passive"))
      (node (ref "U8") (pin "18") (pinfunction "NC_18") (pintype "passive"))
    )
    (net (code "40") (name "Net-(D1-A)") (class "Default")
      (node (ref "D1") (pin "1") (pinfunction "A_1") (pintype "passive"))
      (node (ref "U5") (pin "2") (pinfunction "VOUT_2") (pintype "passive"))
      (node (ref "U5") (pin "4") (pinfunction "VOUT_4") (pintype "passive"))
    )
    (net (code "41") (name "Net-(D2-K)") (class "Default")
      (node (ref "C21") (pin "1") (pinfunction "1_1") (pintype "passive"))
      (node (ref "D2") (pin "1") (pinfunction "K_1") (pintype "passive"))
      (node (ref "L1") (pin "2") (pinfunction "2_2") (pintype "passive"))
      (node (ref "U7") (pin "8") (pinfunction "PH_8") (pintype "passive"))
    )
    (net (code "42") (name "Net-(DATA-CC1)") (class "Default")
      (node (ref "DATA") (pin "A5") (pinfunction "CC1_A5") (pintype "passive"))
      (node (ref "R22") (pin "1") (pinfunction "1_1") (pintype "passive"))
    )
    (net (code "43") (name "Net-(DATA-CC2)") (class "Default")
      (node (ref "DATA") (pin "B5") (pinfunction "CC2_B5") (pintype "passive"))
      (node (ref "R20") (pin "2") (pinfunction "2_2") (pintype "passive"))
    )
    (net (code "44") (name "Net-(PWR-K)") (class "Default")
      (node (ref "PWR") (pin "2") (pinfunction "K_2") (pintype "passive"))
      (node (ref "R19") (pin "2") (pinfunction "2_2") (pintype "passive"))
    )
    (net (code "45") (name "Net-(Q1-B)") (class "Default")
      (node (ref "Q1") (pin "1") (pinfunction "B_1") (pintype "passive"))
      (node (ref "R2") (pin "2") (pinfunction "2_2") (pintype "passive"))
    )
    (net (code "46") (name "Net-(Q2-B)") (class "Default")
      (node (ref "Q2") (pin "1") (pinfunction "B_1") (pintype "passive"))
      (node (ref "R3") (pin "1") (pinfunction "1_1") (pintype "passive"))
    )
    (net (code "47") (name "Net-(R23-Pad1)") (class "Default")
      (node (ref "R23") (pin "1") (pinfunction "1_1") (pintype "passive"))
      (node (ref "R24") (pin "2") (pinfunction "2_2") (pintype "passive"))
    )
    (net (code "48") (name "Net-(U2-CP1)") (class "Default")
      (node (ref "C12") (pin "2") (pinfunction "2_2") (pintype "passive"))
      (node (ref "U2") (pin "1") (pinfunction "CP1_1") (pintype "passive"))
    )
    (net (code "49") (name "Net-(U2-CP2)") (class "Default")
      (node (ref "C12") (pin "1") (pinfunction "1_1") (pintype "passive"))
      (node (ref "U2") (pin "2") (pinfunction "CP2_2") (pintype "passive"))
    )
    (net (code "50") (name "Net-(U2-V3P3OUT)") (class "Default")
      (node (ref "C5") (pin "2") (pinfunction "2_2") (pintype "passive"))
      (node (ref "U2") (pin "15") (pinfunction "V3P3OUT_15") (pintype "passive"))
    )
    (net (code "51") (name "Net-(U2-VCP)") (class "Default")
      (node (ref "C18") (pin "2") (pinfunction "2_2") (pintype "passive"))
      (node (ref "U2") (pin "3") (pinfunction "VCP_3") (pintype "passive"))
    )
    (net (code "52") (name "Net-(U7-BOOT)") (class "Default")
      (node (ref "C21") (pin "2") (pinfunction "2_2") (pintype "passive"))
      (node (ref "U7") (pin "1") (pinfunction "BOOT_1") (pintype "passive"))
    )
    (net (code "53") (name "Net-(U7-VSENSE)") (class "Default")
      (node (ref "R21") (pin "1") (pinfunction "1_1") (pintype "passive"))
      (node (ref "R23") (pin "2") (pinfunction "2_2") (pintype "passive"))
      (node (ref "U7") (pin "4") (pinfunction "VSENSE_4") (pintype "passive"))
    )
    (net (code "54") (name "Net-(U9-VBUS)") (class "Default")
      (node (ref "R17") (pin "1") (pinfunction "1_1") (pintype "passive"))
      (node (ref "U9") (pin "8") (pinfunction "VBUS_8") (pintype "passive"))
    )
    (net (code "55") (name "Net-(U9-VDD)") (class "Default")
      (node (ref "C8") (pin "2") (pinfunction "2_2") (pintype "passive"))
      (node (ref "R18") (pin "1") (pinfunction "1_1") (pintype "passive"))
      (node (ref "U9") (pin "1") (pinfunction "VDD_1") (pintype "passive"))
    )
    (net (code "56") (name "unconnected-(DATA-Pad12)") (class "Default")
      (node (ref "DATA") (pin "12") (pinfunction "12_12") (pintype "passive+no_connect"))
    )
    (net (code "57") (name "unconnected-(DATA-Pad13)") (class "Default")
      (node (ref "DATA") (pin "13") (pinfunction "13_13") (pintype "passive+no_connect"))
    )
    (net (code "58") (name "unconnected-(DATA-Pad14)") (class "Default")
      (node (ref "DATA") (pin "14") (pinfunction "14_14") (pintype "passive+no_connect"))
    )
    (net (code "59") (name "unconnected-(DATA-Pad15)") (class "Default")
      (node (ref "DATA") (pin "15") (pinfunction "15_15") (pintype "passive+no_connect"))
    )
    (net (code "60") (name "unconnected-(DATA-SBU1-PadA8)") (class "Default")
      (node (ref "DATA") (pin "A8") (pinfunction "SBU1_A8") (pintype "passive+no_connect"))
    )
    (net (code "61") (name "unconnected-(DATA-SBU2-PadB8)") (class "Default")
      (node (ref "DATA") (pin "B8") (pinfunction "SBU2_B8") (pintype "passive+no_connect"))
    )
    (net (code "62") (name "unconnected-(PD-DN1-PadA7)") (class "Default")
      (node (ref "PD") (pin "A7") (pinfunction "DN1_A7") (pintype "passive+no_connect"))
    )
    (net (code "63") (name "unconnected-(PD-DN2-PadB7)") (class "Default")
      (node (ref "PD") (pin "B7") (pinfunction "DN2_B7") (pintype "passive+no_connect"))
    )
    (net (code "64") (name "unconnected-(PD-DP1-PadA6)") (class "Default")
      (node (ref "PD") (pin "A6") (pinfunction "DP1_A6") (pintype "passive+no_connect"))
    )
    (net (code "65") (name "unconnected-(PD-DP2-PadB6)") (class "Default")
      (node (ref "PD") (pin "B6") (pinfunction "DP2_B6") (pintype "passive+no_connect"))
    )
    (net (code "66") (name "unconnected-(PD-Pad12)") (class "Default")
      (node (ref "PD") (pin "12") (pinfunction "12_12") (pintype "passive+no_connect"))
    )
    (net (code "67") (name "unconnected-(PD-Pad13)") (class "Default")
      (node (ref "PD") (pin "13") (pinfunction "13_13") (pintype "passive+no_connect"))
    )
    (net (code "68") (name "unconnected-(PD-Pad14)") (class "Default")
      (node (ref "PD") (pin "14") (pinfunction "14_14") (pintype "passive+no_connect"))
    )
    (net (code "69") (name "unconnected-(PD-Pad15)") (class "Default")
      (node (ref "PD") (pin "15") (pinfunction "15_15") (pintype "passive+no_connect"))
    )
    (net (code "70") (name "unconnected-(PD-SBU1-PadA8)") (class "Default")
      (node (ref "PD") (pin "A8") (pinfunction "SBU1_A8") (pintype "passive+no_connect"))
    )
    (net (code "71") (name "unconnected-(PD-SBU2-PadB8)") (class "Default")
      (node (ref "PD") (pin "B8") (pinfunction "SBU2_B8") (pintype "passive+no_connect"))
    )
    (net (code "72") (name "unconnected-(SYSFAN1-Pad3)") (class "Default")
      (node (ref "SYSFAN1") (pin "3") (pinfunction "3_3") (pintype "passive+no_connect"))
    )
    (net (code "73") (name "unconnected-(SYSFAN1-Pad4)") (class "Default")
      (node (ref "SYSFAN1") (pin "4") (pinfunction "4_4") (pintype "passive+no_connect"))
    )
    (net (code "74") (name "unconnected-(U1-EP-Pad17)") (class "Default")
      (node (ref "U1") (pin "17") (pinfunction "EP_17") (pintype "passive+no_connect"))
    )
    (net (code "75") (name "unconnected-(U1-NC-Pad1)") (class "Default")
      (node (ref "U1") (pin "1") (pinfunction "NC_1") (pintype "passive+no_connect"))
    )
    (net (code "76") (name "unconnected-(U1-NC-Pad2)") (class "Default")
      (node (ref "U1") (pin "2") (pinfunction "NC_2") (pintype "passive+no_connect"))
    )
    (net (code "77") (name "unconnected-(U1-NC-Pad3)") (class "Default")
      (node (ref "U1") (pin "3") (pinfunction "NC_3") (pintype "passive+no_connect"))
    )
    (net (code "78") (name "unconnected-(U1-NC-Pad4)") (class "Default")
      (node (ref "U1") (pin "4") (pinfunction "NC_4") (pintype "passive+no_connect"))
    )
    (net (code "79") (name "unconnected-(U1-NC-Pad10)") (class "Default")
      (node (ref "U1") (pin "10") (pinfunction "NC_10") (pintype "passive+no_connect"))
    )
    (net (code "80") (name "unconnected-(U1-OUT-Pad15)") (class "Default")
      (node (ref "U1") (pin "15") (pinfunction "OUT_15") (pintype "passive+no_connect"))
    )
    (net (code "81") (name "unconnected-(U1-PUSH-Pad5)") (class "Default")
      (node (ref "U1") (pin "5") (pinfunction "PUSH_5") (pintype "passive+no_connect"))
    )
    (net (code "82") (name "unconnected-(U1-U-Pad11)") (class "Default")
      (node (ref "U1") (pin "11") (pinfunction "U_11") (pintype "passive+no_connect"))
    )
    (net (code "83") (name "unconnected-(U1-V-Pad12)") (class "Default")
      (node (ref "U1") (pin "12") (pinfunction "V_12") (pintype "passive+no_connect"))
    )
    (net (code "84") (name "unconnected-(U1-W-Pad9)") (class "Default")
      (node (ref "U1") (pin "9") (pinfunction "W_9") (pintype "passive+no_connect"))
    )
    (net (code "85") (name "unconnected-(U2-COMPO#-Pad19)") (class "Default")
      (node (ref "U2") (pin "19") (pinfunction "COMPO#_19") (pintype "passive+no_connect"))
    )
    (net (code "86") (name "unconnected-(U2-NC-Pad21)") (class "Default")
      (node (ref "U2") (pin "21") (pinfunction "NC_21") (pintype "passive+no_connect"))
    )
    (net (code "87") (name "unconnected-(U4-IO2-Pad24)") (class "Default")
      (node (ref "U4") (pin "24") (pinfunction "IO2_24") (pintype "passive+no_connect"))
    )
    (net (code "88") (name "unconnected-(U4-IO5-Pad29)") (class "Default")
      (node (ref "U4") (pin "29") (pinfunction "IO5_29") (pintype "passive+no_connect"))
    )
    (net (code "89") (name "unconnected-(U4-IO12-Pad14)") (class "Default")
      (node (ref "U4") (pin "14") (pinfunction "IO12_14") (pintype "passive+no_connect"))
    )
    (net (code "90") (name "unconnected-(U4-IO13-Pad16)") (class "Default")
      (node (ref "U4") (pin "16") (pinfunction "IO13_16") (pintype "passive+no_connect"))
    )
    (net (code "91") (name "unconnected-(U4-IO15-Pad23)") (class "Default")
      (node (ref "U4") (pin "23") (pinfunction "IO15_23") (pintype "passive+no_connect"))
    )
    (net (code "92") (name "unconnected-(U4-IO16-Pad27)") (class "Default")
      (node (ref "U4") (pin "27") (pinfunction "IO16_27") (pintype "passive+no_connect"))
    )
    (net (code "93") (name "unconnected-(U4-IO17-Pad28)") (class "Default")
      (node (ref "U4") (pin "28") (pinfunction "IO17_28") (pintype "passive+no_connect"))
    )
    (net (code "94") (name "unconnected-(U4-IO18-Pad30)") (class "Default")
      (node (ref "U4") (pin "30") (pinfunction "IO18_30") (pintype "passive+no_connect"))
    )
    (net (code "95") (name "unconnected-(U4-IO19-Pad31)") (class "Default")
      (node (ref "U4") (pin "31") (pinfunction "IO19_31") (pintype "passive+no_connect"))
    )
    (net (code "96") (name "unconnected-(U4-NC-Pad17)") (class "Default")
      (node (ref "U4") (pin "17") (pinfunction "NC_17") (pintype "passive+no_connect"))
    )
    (net (code "97") (name "unconnected-(U4-NC-Pad18)") (class "Default")
      (node (ref "U4") (pin "18") (pinfunction "NC_18") (pintype "passive+no_connect"))
    )
    (net (code "98") (name "unconnected-(U4-NC-Pad19)") (class "Default")
      (node (ref "U4") (pin "19") (pinfunction "NC_19") (pintype "passive+no_connect"))
    )
    (net (code "99") (name "unconnected-(U4-NC-Pad20)") (class "Default")
      (node (ref "U4") (pin "20") (pinfunction "NC_20") (pintype "passive+no_connect"))
    )
    (net (code "100") (name "unconnected-(U4-NC-Pad21)") (class "Default")
      (node (ref "U4") (pin "21") (pinfunction "NC_21") (pintype "passive+no_connect"))
    )
    (net (code "101") (name "unconnected-(U4-NC-Pad22)") (class "Default")
      (node (ref "U4") (pin "22") (pinfunction "NC_22") (pintype "passive+no_connect"))
    )
    (net (code "102") (name "unconnected-(U4-NC-Pad32)") (class "Default")
      (node (ref "U4") (pin "32") (pinfunction "NC_32") (pintype "passive+no_connect"))
    )
    (net (code "103") (name "unconnected-(U7-ENA-Pad5)") (class "Default")
      (node (ref "U7") (pin "5") (pinfunction "ENA_5") (pintype "passive+no_connect"))
    )
    (net (code "104") (name "unconnected-(U7-NC-Pad2)") (class "Default")
      (node (ref "U7") (pin "2") (pinfunction "NC_2") (pintype "passive+no_connect"))
    )
    (net (code "105") (name "unconnected-(U7-NC-Pad3)") (class "Default")
      (node (ref "U7") (pin "3") (pinfunction "NC_3") (pintype "passive+no_connect"))
    )
    (net (code "106") (name "unconnected-(U8-CTS-Pad23)") (class "Default")
      (node (ref "U8") (pin "23") (pinfunction "CTS_23") (pintype "passive+no_connect"))
    )
    (net (code "107") (name "unconnected-(U8-DCD-Pad1)") (class "Default")
      (node (ref "U8") (pin "1") (pinfunction "DCD_1") (pintype "passive+no_connect"))
    )
    (net (code "108") (name "unconnected-(U8-DSR-Pad27)") (class "Default")
      (node (ref "U8") (pin "27") (pinfunction "DSR_27") (pintype "passive+no_connect"))
    )
    (net (code "109") (name "unconnected-(U8-NC-Pad10)") (class "Default")
      (node (ref "U8") (pin "10") (pinfunction "NC_10") (pintype "passive+no_connect"))
    )
    (net (code "110") (name "unconnected-(U8-NC-Pad13)") (class "Default")
      (node (ref "U8") (pin "13") (pinfunction "NC_13") (pintype "passive+no_connect"))
    )
    (net (code "111") (name "unconnected-(U8-NC-Pad14)") (class "Default")
      (node (ref "U8") (pin "14") (pinfunction "NC_14") (pintype "passive+no_connect"))
    )
    (net (code "112") (name "unconnected-(U8-NC-Pad15)") (class "Default")
      (node (ref "U8") (pin "15") (pinfunction "NC_15") (pintype "passive+no_connect"))
    )
    (net (code "113") (name "unconnected-(U8-NC-Pad16)") (class "Default")
      (node (ref "U8") (pin "16") (pinfunction "NC_16") (pintype "passive+no_connect"))
    )
    (net (code "114") (name "unconnected-(U8-NC-Pad17)") (class "Default")
      (node (ref "U8") (pin "17") (pinfunction "NC_17") (pintype "passive+no_connect"))
    )
    (net (code "115") (name "unconnected-(U8-NC-Pad19)") (class "Default")
      (node (ref "U8") (pin "19") (pinfunction "NC_19") (pintype "passive+no_connect"))
    )
    (net (code "116") (name "unconnected-(U8-NC-Pad20)") (class "Default")
      (node (ref "U8") (pin "20") (pinfunction "NC_20") (pintype "passive+no_connect"))
    )
    (net (code "117") (name "unconnected-(U8-NC-Pad21)") (class "Default")
      (node (ref "U8") (pin "21") (pinfunction "NC_21") (pintype "passive+no_connect"))
    )
    (net (code "118") (name "unconnected-(U8-NC-Pad22)") (class "Default")
      (node (ref "U8") (pin "22") (pinfunction "NC_22") (pintype "passive+no_connect"))
    )
    (net (code "119") (name "unconnected-(U8-RI-Pad2)") (class "Default")
      (node (ref "U8") (pin "2") (pinfunction "RI_2") (pintype "passive+no_connect"))
    )
    (net (code "120") (name "unconnected-(U8-SUSPEND#-Pad11)") (class "Default")
      (node (ref "U8") (pin "11") (pinfunction "SUSPEND#_11") (pintype "passive+no_connect"))
    )
    (net (code "121") (name "unconnected-(U8-SUSPEND-Pad12)") (class "Default")
      (node (ref "U8") (pin "12") (pinfunction "SUSPEND_12") (pintype "passive+no_connect"))
    )
    (net (code "122") (name "unconnected-(U9-CFG1-Pad9)") (class "Default")
      (node (ref "U9") (pin "9") (pinfunction "CFG1_9") (pintype "passive+no_connect"))
    )
    (net (code "123") (name "unconnected-(U9-CFG2-Pad2)") (class "Default")
      (node (ref "U9") (pin "2") (pinfunction "CFG2_2") (pintype "passive+no_connect"))
    )
    (net (code "124") (name "unconnected-(U9-CFG3-Pad3)") (class "Default")
      (node (ref "U9") (pin "3") (pinfunction "CFG3_3") (pintype "passive+no_connect"))
    )
    (net (code "125") (name "unconnected-(U9-DM-Pad5)") (class "Default")
      (node (ref "U9") (pin "5") (pinfunction "DM_5") (pintype "passive+no_connect"))
    )
    (net (code "126") (name "unconnected-(U9-DP-Pad4)") (class "Default")
      (node (ref "U9") (pin "4") (pinfunction "DP_4") (pintype "passive+no_connect"))
    )
    (net (code "127") (name "unconnected-(U9-PG-Pad10)") (class "Default")
      (node (ref "U9") (pin "10") (pinfunction "PG_10") (pintype "passive+no_connect"))
    )
  )
)
